# badge5.net
KiCad netlist of a schematic drawn in Altium Designer
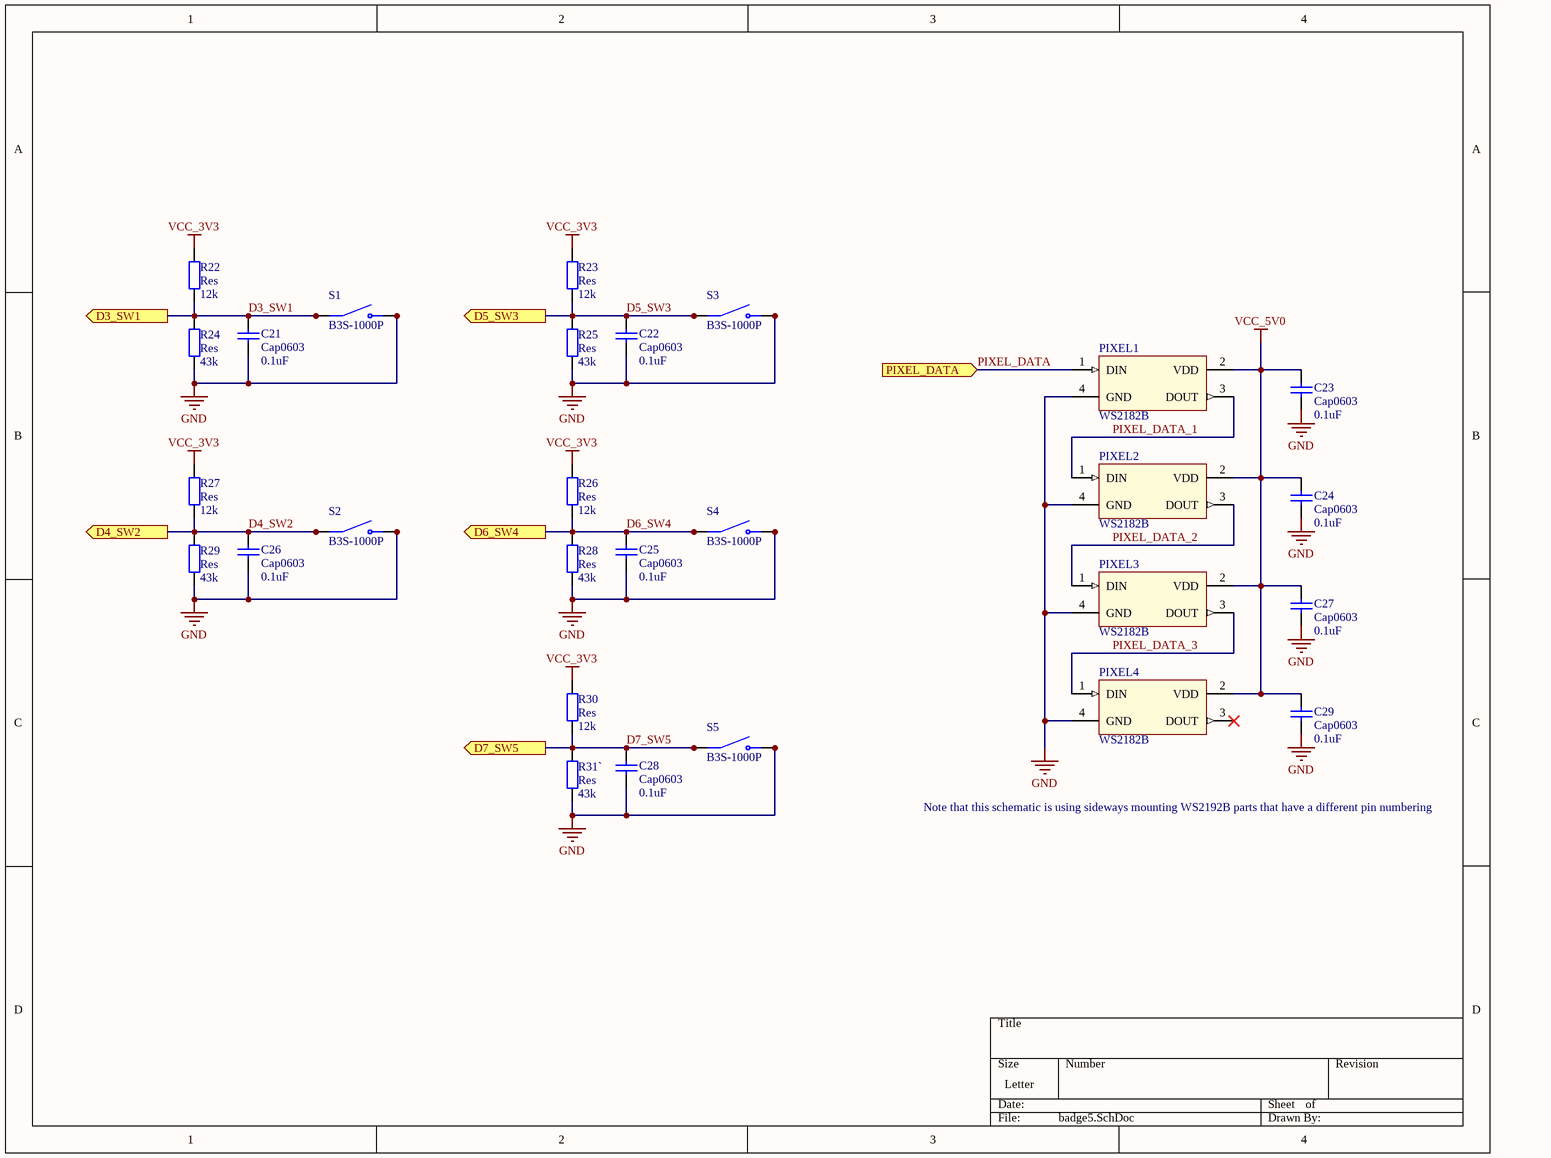
[diagram p0: badge5.SchDoc]

(export (version "E")
  (design (tool "Eeschema 10.0.6"))
  (components
    (comp (ref "C21")
      (value "Cap0603")
      (footprint "C0603")
      (description "Capacitor")
      (fields
        (field (name "ALTIUM_VALUE") "0.1uF")
        (field (name "MF") "KEMET")
        (field (name "MP") "C0603C104Z3VACTU")
        (field (name "PUBLISHER") "Altium Limited")
      )
      (libsource (lib "badge") (part "Cap0603"))
    )
    (comp (ref "C22")
      (value "Cap0603")
      (footprint "C0603")
      (description "Capacitor")
      (fields
        (field (name "ALTIUM_VALUE") "0.1uF")
        (field (name "MF") "KEMET")
        (field (name "MP") "C0603C104Z3VACTU")
        (field (name "PUBLISHER") "Altium Limited")
      )
      (libsource (lib "badge") (part "Cap0603"))
    )
    (comp (ref "C23")
      (value "Cap0603")
      (footprint "C0603")
      (description "Capacitor")
      (fields
        (field (name "ALTIUM_VALUE") "0.1uF")
        (field (name "MF") "KEMET")
        (field (name "MP") "C0603C104Z3VACTU")
        (field (name "PUBLISHER") "Altium Limited")
      )
      (libsource (lib "badge") (part "Cap0603"))
    )
    (comp (ref "C24")
      (value "Cap0603")
      (footprint "C0603")
      (description "Capacitor")
      (fields
        (field (name "ALTIUM_VALUE") "0.1uF")
        (field (name "MF") "KEMET")
        (field (name "MP") "C0603C104Z3VACTU")
        (field (name "PUBLISHER") "Altium Limited")
      )
      (libsource (lib "badge") (part "Cap0603"))
    )
    (comp (ref "C25")
      (value "Cap0603")
      (footprint "C0603")
      (description "Capacitor")
      (fields
        (field (name "ALTIUM_VALUE") "0.1uF")
        (field (name "MF") "KEMET")
        (field (name "MP") "C0603C104Z3VACTU")
        (field (name "PUBLISHER") "Altium Limited")
      )
      (libsource (lib "badge") (part "Cap0603"))
    )
    (comp (ref "C26")
      (value "Cap0603")
      (footprint "C0603")
      (description "Capacitor")
      (fields
        (field (name "ALTIUM_VALUE") "0.1uF")
        (field (name "MF") "KEMET")
        (field (name "MP") "C0603C104Z3VACTU")
        (field (name "PUBLISHER") "Altium Limited")
      )
      (libsource (lib "badge") (part "Cap0603"))
    )
    (comp (ref "C27")
      (value "Cap0603")
      (footprint "C0603")
      (description "Capacitor")
      (fields
        (field (name "ALTIUM_VALUE") "0.1uF")
        (field (name "MF") "KEMET")
        (field (name "MP") "C0603C104Z3VACTU")
        (field (name "PUBLISHER") "Altium Limited")
      )
      (libsource (lib "badge") (part "Cap0603"))
    )
    (comp (ref "C28")
      (value "Cap0603")
      (footprint "C0603")
      (description "Capacitor")
      (fields
        (field (name "ALTIUM_VALUE") "0.1uF")
        (field (name "MF") "KEMET")
        (field (name "MP") "C0603C104Z3VACTU")
        (field (name "PUBLISHER") "Altium Limited")
      )
      (libsource (lib "badge") (part "Cap0603"))
    )
    (comp (ref "C29")
      (value "Cap0603")
      (footprint "C0603")
      (description "Capacitor")
      (fields
        (field (name "ALTIUM_VALUE") "0.1uF")
        (field (name "MF") "KEMET")
        (field (name "MP") "C0603C104Z3VACTU")
        (field (name "PUBLISHER") "Altium Limited")
      )
      (libsource (lib "badge") (part "Cap0603"))
    )
    (comp (ref "PIXEL1")
      (value "WS2182B")
      (footprint "WS2812B_SIDE")
      (fields (field (name "MF") "DNP"))
      (libsource (lib "badge") (part "WS2182B"))
    )
    (comp (ref "PIXEL2")
      (value "WS2182B")
      (footprint "WS2812B_SIDE")
      (fields (field (name "MF") "DNP"))
      (libsource (lib "badge") (part "WS2182B"))
    )
    (comp (ref "PIXEL3")
      (value "WS2182B")
      (footprint "WS2812B_SIDE")
      (fields (field (name "MF") "DNP"))
      (libsource (lib "badge") (part "WS2182B"))
    )
    (comp (ref "PIXEL4")
      (value "WS2182B")
      (footprint "WS2812B_SIDE")
      (fields (field (name "MF") "DNP"))
      (libsource (lib "badge") (part "WS2182B"))
    )
    (comp (ref "R22")
      (value "Res")
      (footprint "R0603")
      (description "Resistor")
      (fields
        (field (name "ALTIUM_VALUE") "12k")
        (field (name "MP") "RC0603JR-0712KL")
        (field (name "MF") "Yageo")
        (field (name "PUBLISHER") "Altium Limited")
      )
      (libsource (lib "badge") (part "Res"))
    )
    (comp (ref "R23")
      (value "Res")
      (footprint "R0603")
      (description "Resistor")
      (fields
        (field (name "ALTIUM_VALUE") "12k")
        (field (name "MP") "RC0603JR-0712KL")
        (field (name "MF") "Yageo")
        (field (name "PUBLISHER") "Altium Limited")
      )
      (libsource (lib "badge") (part "Res"))
    )
    (comp (ref "R24")
      (value "Res")
      (footprint "R0603")
      (description "Resistor")
      (fields
        (field (name "ALTIUM_VALUE") "43k")
        (field (name "MF") "Yageo")
        (field (name "MP") "RC0603JR-0743KL")
        (field (name "PUBLISHER") "Altium Limited")
      )
      (libsource (lib "badge") (part "Res"))
    )
    (comp (ref "R25")
      (value "Res")
      (footprint "R0603")
      (description "Resistor")
      (fields
        (field (name "ALTIUM_VALUE") "43k")
        (field (name "MF") "Yageo")
        (field (name "MP") "RC0603JR-0743KL")
        (field (name "PUBLISHER") "Altium Limited")
      )
      (libsource (lib "badge") (part "Res"))
    )
    (comp (ref "R26")
      (value "Res")
      (footprint "R0603")
      (description "Resistor")
      (fields
        (field (name "ALTIUM_VALUE") "12k")
        (field (name "MP") "RC0603JR-0712KL")
        (field (name "MF") "Yageo")
        (field (name "PUBLISHER") "Altium Limited")
      )
      (libsource (lib "badge") (part "Res"))
    )
    (comp (ref "R27")
      (value "Res")
      (footprint "R0603")
      (description "Resistor")
      (fields
        (field (name "ALTIUM_VALUE") "12k")
        (field (name "MP") "RC0603JR-0712KL")
        (field (name "MF") "Yageo")
        (field (name "PUBLISHER") "Altium Limited")
      )
      (libsource (lib "badge") (part "Res"))
    )
    (comp (ref "R28")
      (value "Res")
      (footprint "R0603")
      (description "Resistor")
      (fields
        (field (name "ALTIUM_VALUE") "43k")
        (field (name "MF") "Yageo")
        (field (name "MP") "RC0603JR-0743KL")
        (field (name "PUBLISHER") "Altium Limited")
      )
      (libsource (lib "badge") (part "Res"))
    )
    (comp (ref "R29")
      (value "Res")
      (footprint "R0603")
      (description "Resistor")
      (fields
        (field (name "ALTIUM_VALUE") "43k")
        (field (name "MF") "Yageo")
        (field (name "MP") "RC0603JR-0743KL")
        (field (name "PUBLISHER") "Altium Limited")
      )
      (libsource (lib "badge") (part "Res"))
    )
    (comp (ref "R30")
      (value "Res")
      (footprint "R0603")
      (description "Resistor")
      (fields
        (field (name "ALTIUM_VALUE") "12k")
        (field (name "MP") "RC0603JR-0712KL")
        (field (name "MF") "Yageo")
        (field (name "PUBLISHER") "Altium Limited")
      )
      (libsource (lib "badge") (part "Res"))
    )
    (comp (ref "R31`")
      (value "Res")
      (footprint "R0603")
      (description "Resistor")
      (fields
        (field (name "ALTIUM_VALUE") "43k")
        (field (name "MF") "Yageo")
        (field (name "MP") "RC0603JR-0743KL")
        (field (name "PUBLISHER") "Altium Limited")
      )
      (libsource (lib "badge") (part "Res"))
    )
    (comp (ref "S1")
      (value "B3S-1000P")
      (footprint "SW_B3S-1000P")
      (description "Tactile Switch SPST-NO Top Actuated Surface Mount")
      (fields (field (name "MF") "Omron Electronics"))
      (libsource (lib "badge") (part "B3S-1000P"))
    )
    (comp (ref "S2")
      (value "B3S-1000P")
      (footprint "SW_B3S-1000P")
      (description "Tactile Switch SPST-NO Top Actuated Surface Mount")
      (fields (field (name "MF") "Omron Electronics"))
      (libsource (lib "badge") (part "B3S-1000P"))
    )
    (comp (ref "S3")
      (value "B3S-1000P")
      (footprint "SW_B3S-1000P")
      (description "Tactile Switch SPST-NO Top Actuated Surface Mount")
      (fields (field (name "MF") "Omron Electronics"))
      (libsource (lib "badge") (part "B3S-1000P"))
    )
    (comp (ref "S4")
      (value "B3S-1000P")
      (footprint "SW_B3S-1000P")
      (description "Tactile Switch SPST-NO Top Actuated Surface Mount")
      (fields (field (name "MF") "Omron Electronics"))
      (libsource (lib "badge") (part "B3S-1000P"))
    )
    (comp (ref "S5")
      (value "B3S-1000P")
      (footprint "SW_B3S-1000P")
      (description "Tactile Switch SPST-NO Top Actuated Surface Mount")
      (fields (field (name "MF") "Omron Electronics"))
      (libsource (lib "badge") (part "B3S-1000P"))
    )
  )
  (nets
    (net (code "1") (name "/D3_SW1") (class "Default")
      (node (ref "C21") (pin "2") (pinfunction "2_2") (pintype "passive"))
      (node (ref "R22") (pin "1") (pinfunction "1_1") (pintype "passive"))
      (node (ref "R24") (pin "2") (pinfunction "2_2") (pintype "passive"))
      (node (ref "S1") (pin "1") (pinfunction "COM_1") (pintype "passive"))
      (node (ref "S1") (pin "2") (pinfunction "COM_2") (pintype "passive"))
    )
    (net (code "2") (name "/D4_SW2") (class "Default")
      (node (ref "C26") (pin "2") (pinfunction "2_2") (pintype "passive"))
      (node (ref "R27") (pin "1") (pinfunction "1_1") (pintype "passive"))
      (node (ref "R29") (pin "2") (pinfunction "2_2") (pintype "passive"))
      (node (ref "S2") (pin "1") (pinfunction "COM_1") (pintype "passive"))
      (node (ref "S2") (pin "2") (pinfunction "COM_2") (pintype "passive"))
    )
    (net (code "3") (name "/D5_SW3") (class "Default")
      (node (ref "C22") (pin "2") (pinfunction "2_2") (pintype "passive"))
      (node (ref "R23") (pin "1") (pinfunction "1_1") (pintype "passive"))
      (node (ref "R25") (pin "2") (pinfunction "2_2") (pintype "passive"))
      (node (ref "S3") (pin "1") (pinfunction "COM_1") (pintype "passive"))
      (node (ref "S3") (pin "2") (pinfunction "COM_2") (pintype "passive"))
    )
    (net (code "4") (name "/D6_SW4") (class "Default")
      (node (ref "C25") (pin "2") (pinfunction "2_2") (pintype "passive"))
      (node (ref "R26") (pin "1") (pinfunction "1_1") (pintype "passive"))
      (node (ref "R28") (pin "2") (pinfunction "2_2") (pintype "passive"))
      (node (ref "S4") (pin "1") (pinfunction "COM_1") (pintype "passive"))
      (node (ref "S4") (pin "2") (pinfunction "COM_2") (pintype "passive"))
    )
    (net (code "5") (name "/D7_SW5") (class "Default")
      (node (ref "C28") (pin "2") (pinfunction "2_2") (pintype "passive"))
      (node (ref "R30") (pin "1") (pinfunction "1_1") (pintype "passive"))
      (node (ref "R31`") (pin "2") (pinfunction "2_2") (pintype "passive"))
      (node (ref "S5") (pin "1") (pinfunction "COM_1") (pintype "passive"))
      (node (ref "S5") (pin "2") (pinfunction "COM_2") (pintype "passive"))
    )
    (net (code "6") (name "/PIXEL_DATA") (class "Default")
      (node (ref "PIXEL1") (pin "1") (pinfunction "DIN_1") (pintype "input"))
    )
    (net (code "7") (name "/PIXEL_DATA_1") (class "Default")
      (node (ref "PIXEL1") (pin "3") (pinfunction "DOUT_3") (pintype "output"))
      (node (ref "PIXEL2") (pin "1") (pinfunction "DIN_1") (pintype "input"))
    )
    (net (code "8") (name "/PIXEL_DATA_2") (class "Default")
      (node (ref "PIXEL2") (pin "3") (pinfunction "DOUT_3") (pintype "output"))
      (node (ref "PIXEL3") (pin "1") (pinfunction "DIN_1") (pintype "input"))
    )
    (net (code "9") (name "/PIXEL_DATA_3") (class "Default")
      (node (ref "PIXEL3") (pin "3") (pinfunction "DOUT_3") (pintype "output"))
      (node (ref "PIXEL4") (pin "1") (pinfunction "DIN_1") (pintype "input"))
    )
    (net (code "10") (name "GND") (class "Default")
      (node (ref "C21") (pin "1") (pinfunction "1_1") (pintype "passive"))
      (node (ref "C22") (pin "1") (pinfunction "1_1") (pintype "passive"))
      (node (ref "C23") (pin "1") (pinfunction "1_1") (pintype "passive"))
      (node (ref "C24") (pin "1") (pinfunction "1_1") (pintype "passive"))
      (node (ref "C25") (pin "1") (pinfunction "1_1") (pintype "passive"))
      (node (ref "C26") (pin "1") (pinfunction "1_1") (pintype "passive"))
      (node (ref "C27") (pin "1") (pinfunction "1_1") (pintype "passive"))
      (node (ref "C28") (pin "1") (pinfunction "1_1") (pintype "passive"))
      (node (ref "C29") (pin "1") (pinfunction "1_1") (pintype "passive"))
      (node (ref "PIXEL1") (pin "4") (pinfunction "GND_4") (pintype "power_in"))
      (node (ref "PIXEL2") (pin "4") (pinfunction "GND_4") (pintype "power_in"))
      (node (ref "PIXEL3") (pin "4") (pinfunction "GND_4") (pintype "power_in"))
      (node (ref "PIXEL4") (pin "4") (pinfunction "GND_4") (pintype "power_in"))
      (node (ref "R24") (pin "1") (pinfunction "1_1") (pintype "passive"))
      (node (ref "R25") (pin "1") (pinfunction "1_1") (pintype "passive"))
      (node (ref "R28") (pin "1") (pinfunction "1_1") (pintype "passive"))
      (node (ref "R29") (pin "1") (pinfunction "1_1") (pintype "passive"))
      (node (ref "R31`") (pin "1") (pinfunction "1_1") (pintype "passive"))
      (node (ref "S1") (pin "3") (pinfunction "NO_3") (pintype "passive"))
      (node (ref "S1") (pin "4") (pinfunction "NO_4") (pintype "passive"))
      (node (ref "S2") (pin "3") (pinfunction "NO_3") (pintype "passive"))
      (node (ref "S2") (pin "4") (pinfunction "NO_4") (pintype "passive"))
      (node (ref "S3") (pin "3") (pinfunction "NO_3") (pintype "passive"))
      (node (ref "S3") (pin "4") (pinfunction "NO_4") (pintype "passive"))
      (node (ref "S4") (pin "3") (pinfunction "NO_3") (pintype "passive"))
      (node (ref "S4") (pin "4") (pinfunction "NO_4") (pintype "passive"))
      (node (ref "S5") (pin "3") (pinfunction "NO_3") (pintype "passive"))
      (node (ref "S5") (pin "4") (pinfunction "NO_4") (pintype "passive"))
    )
    (net (code "11") (name "VCC_3V3") (class "Default")
      (node (ref "R22") (pin "2") (pinfunction "2_2") (pintype "passive"))
      (node (ref "R23") (pin "2") (pinfunction "2_2") (pintype "passive"))
      (node (ref "R26") (pin "2") (pinfunction "2_2") (pintype "passive"))
      (node (ref "R27") (pin "2") (pinfunction "2_2") (pintype "passive"))
      (node (ref "R30") (pin "2") (pinfunction "2_2") (pintype "passive"))
    )
    (net (code "12") (name "VCC_5V0") (class "Default")
      (node (ref "C23") (pin "2") (pinfunction "2_2") (pintype "passive"))
      (node (ref "C24") (pin "2") (pinfunction "2_2") (pintype "passive"))
      (node (ref "C27") (pin "2") (pinfunction "2_2") (pintype "passive"))
      (node (ref "C29") (pin "2") (pinfunction "2_2") (pintype "passive"))
      (node (ref "PIXEL1") (pin "2") (pinfunction "VDD_2") (pintype "power_in"))
      (node (ref "PIXEL2") (pin "2") (pinfunction "VDD_2") (pintype "power_in"))
      (node (ref "PIXEL3") (pin "2") (pinfunction "VDD_2") (pintype "power_in"))
      (node (ref "PIXEL4") (pin "2") (pinfunction "VDD_2") (pintype "power_in"))
    )
    (net (code "13") (name "unconnected-(PIXEL4-DOUT-Pad3)") (class "Default")
      (node (ref "PIXEL4") (pin "3") (pinfunction "DOUT_3") (pintype "output+no_connect"))
    )
  )
)
